# main.net
KiCad netlist of a schematic drawn in EAGLE
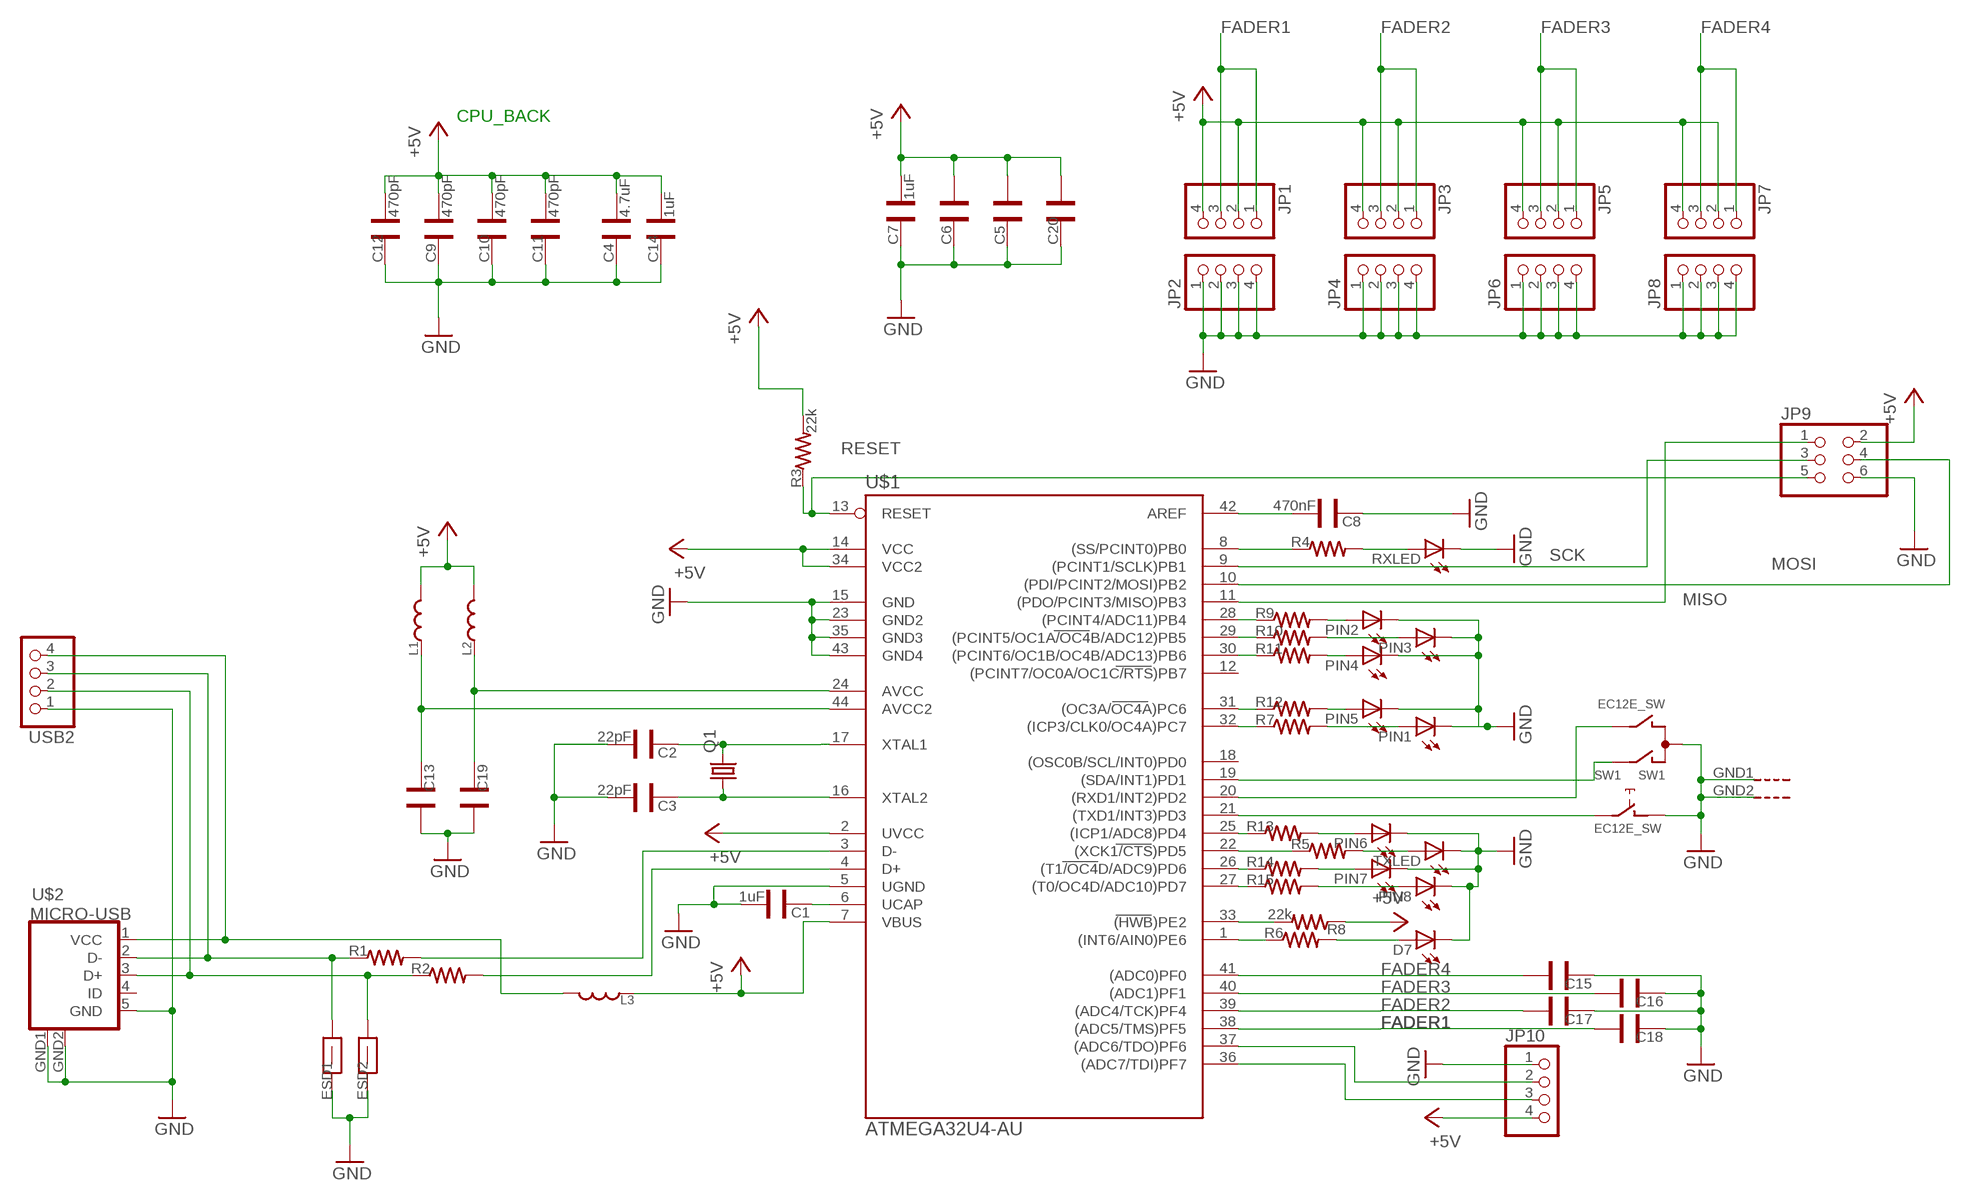
[diagram p0: schematic, sheet 1]

(export (version "E")
  (design (tool "Eeschema 10.0.6"))
  (components
    (comp (ref "C1")
      (value "1uF")
      (footprint "eagle-import:CAP-0805")
      (libsource (lib "eagle-import") (part "CAP0805"))
    )
    (comp (ref "C2")
      (value "22pF")
      (footprint "eagle-import:CAP-0603")
      (libsource (lib "eagle-import") (part "CAP0603"))
    )
    (comp (ref "C3")
      (value "22pF")
      (footprint "eagle-import:CAP-0603")
      (libsource (lib "eagle-import") (part "CAP0603"))
    )
    (comp (ref "C4")
      (value "4.7uF")
      (footprint "eagle-import:CAP-0805")
      (libsource (lib "eagle-import") (part "CAP0805"))
    )
    (comp (ref "C5")
      (value "CAP0805")
      (footprint "eagle-import:CAP-0805")
      (libsource (lib "eagle-import") (part "CAP0805"))
    )
    (comp (ref "C6")
      (value "CAP0805")
      (footprint "eagle-import:CAP-0805")
      (libsource (lib "eagle-import") (part "CAP0805"))
    )
    (comp (ref "C7")
      (value "1uF")
      (footprint "eagle-import:CAP-0805")
      (libsource (lib "eagle-import") (part "CAP0805"))
    )
    (comp (ref "C8")
      (value "470nF")
      (footprint "eagle-import:CAP-0603")
      (libsource (lib "eagle-import") (part "CAP0603"))
    )
    (comp (ref "C9")
      (value "470pF")
      (footprint "eagle-import:CAP-0603")
      (libsource (lib "eagle-import") (part "CAP0603"))
    )
    (comp (ref "C10")
      (value "470pF")
      (footprint "eagle-import:CAP-0603")
      (libsource (lib "eagle-import") (part "CAP0603"))
    )
    (comp (ref "C11")
      (value "470pF")
      (footprint "eagle-import:CAP-0603")
      (libsource (lib "eagle-import") (part "CAP0603"))
    )
    (comp (ref "C12")
      (value "470pF")
      (footprint "eagle-import:CAP-0603")
      (libsource (lib "eagle-import") (part "CAP0603"))
    )
    (comp (ref "C13")
      (value "CAP0805")
      (footprint "eagle-import:CAP-0805")
      (libsource (lib "eagle-import") (part "CAP0805"))
    )
    (comp (ref "C14")
      (value "1uF")
      (footprint "eagle-import:CAP-0805")
      (libsource (lib "eagle-import") (part "CAP0805"))
    )
    (comp (ref "C15")
      (value "CAP0603")
      (footprint "eagle-import:CAP-0603")
      (libsource (lib "eagle-import") (part "CAP0603"))
    )
    (comp (ref "C16")
      (value "CAP0603")
      (footprint "eagle-import:CAP-0603")
      (libsource (lib "eagle-import") (part "CAP0603"))
    )
    (comp (ref "C17")
      (value "CAP0603")
      (footprint "eagle-import:CAP-0603")
      (libsource (lib "eagle-import") (part "CAP0603"))
    )
    (comp (ref "C18")
      (value "CAP0603")
      (footprint "eagle-import:CAP-0603")
      (libsource (lib "eagle-import") (part "CAP0603"))
    )
    (comp (ref "C19")
      (value "CAP0805")
      (footprint "eagle-import:CAP-0805")
      (libsource (lib "eagle-import") (part "CAP0805"))
    )
    (comp (ref "C20")
      (value "CAP0805")
      (footprint "eagle-import:CAP-0805")
      (libsource (lib "eagle-import") (part "CAP0805"))
    )
    (comp (ref "D7")
      (value "LED0603")
      (footprint "eagle-import:LED-0603")
      (libsource (lib "eagle-import") (part "LED0603"))
    )
    (comp (ref "ESD1")
      (value "FB")
      (footprint "eagle-import:FB-0603")
      (libsource (lib "eagle-import") (part "FB"))
    )
    (comp (ref "ESD2")
      (value "FB")
      (footprint "eagle-import:FB-0603")
      (libsource (lib "eagle-import") (part "FB"))
    )
    (comp (ref "JP1")
      (value "PINHD-1X4")
      (footprint "eagle-import:1X04")
      (libsource (lib "eagle-import") (part "PINHD-1X4"))
    )
    (comp (ref "JP2")
      (value "PINHD-1X4")
      (footprint "eagle-import:1X04")
      (libsource (lib "eagle-import") (part "PINHD-1X4"))
    )
    (comp (ref "JP3")
      (value "PINHD-1X4")
      (footprint "eagle-import:1X04")
      (libsource (lib "eagle-import") (part "PINHD-1X4"))
    )
    (comp (ref "JP4")
      (value "PINHD-1X4")
      (footprint "eagle-import:1X04")
      (libsource (lib "eagle-import") (part "PINHD-1X4"))
    )
    (comp (ref "JP5")
      (value "PINHD-1X4")
      (footprint "eagle-import:1X04")
      (libsource (lib "eagle-import") (part "PINHD-1X4"))
    )
    (comp (ref "JP6")
      (value "PINHD-1X4")
      (footprint "eagle-import:1X04")
      (libsource (lib "eagle-import") (part "PINHD-1X4"))
    )
    (comp (ref "JP7")
      (value "PINHD-1X4")
      (footprint "eagle-import:1X04")
      (libsource (lib "eagle-import") (part "PINHD-1X4"))
    )
    (comp (ref "JP8")
      (value "PINHD-1X4")
      (footprint "eagle-import:1X04")
      (libsource (lib "eagle-import") (part "PINHD-1X4"))
    )
    (comp (ref "JP9")
      (value "PINHD-2X3")
      (footprint "eagle-import:2X03")
      (libsource (lib "eagle-import") (part "PINHD-2X3"))
    )
    (comp (ref "JP10")
      (value "PINHD-1X4")
      (footprint "eagle-import:1X04")
      (libsource (lib "eagle-import") (part "PINHD-1X4"))
    )
    (comp (ref "L1")
      (value "IND0603")
      (footprint "eagle-import:IND-0603")
      (libsource (lib "eagle-import") (part "IND0603"))
    )
    (comp (ref "L2")
      (value "IND0603")
      (footprint "eagle-import:IND-0603")
      (libsource (lib "eagle-import") (part "IND0603"))
    )
    (comp (ref "L3")
      (value "IND0603")
      (footprint "eagle-import:IND-0603")
      (libsource (lib "eagle-import") (part "IND0603"))
    )
    (comp (ref "PIN1")
      (value "LED0603")
      (footprint "eagle-import:LED-0603")
      (libsource (lib "eagle-import") (part "LED0603"))
    )
    (comp (ref "PIN2")
      (value "LED0603")
      (footprint "eagle-import:LED-0603")
      (libsource (lib "eagle-import") (part "LED0603"))
    )
    (comp (ref "PIN3")
      (value "LED0603")
      (footprint "eagle-import:LED-0603")
      (libsource (lib "eagle-import") (part "LED0603"))
    )
    (comp (ref "PIN4")
      (value "LED0603")
      (footprint "eagle-import:LED-0603")
      (libsource (lib "eagle-import") (part "LED0603"))
    )
    (comp (ref "PIN5")
      (value "LED0603")
      (footprint "eagle-import:LED-0603")
      (libsource (lib "eagle-import") (part "LED0603"))
    )
    (comp (ref "PIN6")
      (value "LED0603")
      (footprint "eagle-import:LED-0603")
      (libsource (lib "eagle-import") (part "LED0603"))
    )
    (comp (ref "PIN7")
      (value "LED0603")
      (footprint "eagle-import:LED-0603")
      (libsource (lib "eagle-import") (part "LED0603"))
    )
    (comp (ref "PIN8")
      (value "LED0603")
      (footprint "eagle-import:LED-0603")
      (libsource (lib "eagle-import") (part "LED0603"))
    )
    (comp (ref "Q1")
      (value "CRYSTALHC49S")
      (footprint "eagle-import:HC49_S")
      (libsource (lib "eagle-import") (part "CRYSTALHC49S"))
    )
    (comp (ref "R1")
      (value "RES0603")
      (footprint "eagle-import:RES-0603")
      (libsource (lib "eagle-import") (part "RES0603"))
    )
    (comp (ref "R2")
      (value "RES0603")
      (footprint "eagle-import:RES-0603")
      (libsource (lib "eagle-import") (part "RES0603"))
    )
    (comp (ref "R3")
      (value "22k")
      (footprint "eagle-import:RES-0603")
      (libsource (lib "eagle-import") (part "RES0603"))
    )
    (comp (ref "R4")
      (value "RES0603")
      (footprint "eagle-import:RES-0603")
      (libsource (lib "eagle-import") (part "RES0603"))
    )
    (comp (ref "R5")
      (value "RES0603")
      (footprint "eagle-import:RES-0603")
      (libsource (lib "eagle-import") (part "RES0603"))
    )
    (comp (ref "R6")
      (value "RES0603")
      (footprint "eagle-import:RES-0603")
      (libsource (lib "eagle-import") (part "RES0603"))
    )
    (comp (ref "R7")
      (value "RES0603")
      (footprint "eagle-import:RES-0603")
      (libsource (lib "eagle-import") (part "RES0603"))
    )
    (comp (ref "R8")
      (value "22k")
      (footprint "eagle-import:RES-0603")
      (libsource (lib "eagle-import") (part "RES0603"))
    )
    (comp (ref "R9")
      (value "RES0603")
      (footprint "eagle-import:RES-0603")
      (libsource (lib "eagle-import") (part "RES0603"))
    )
    (comp (ref "R10")
      (value "RES0603")
      (footprint "eagle-import:RES-0603")
      (libsource (lib "eagle-import") (part "RES0603"))
    )
    (comp (ref "R11")
      (value "RES0603")
      (footprint "eagle-import:RES-0603")
      (libsource (lib "eagle-import") (part "RES0603"))
    )
    (comp (ref "R12")
      (value "RES0603")
      (footprint "eagle-import:RES-0603")
      (libsource (lib "eagle-import") (part "RES0603"))
    )
    (comp (ref "R13")
      (value "RES0603")
      (footprint "eagle-import:RES-0603")
      (libsource (lib "eagle-import") (part "RES0603"))
    )
    (comp (ref "R14")
      (value "RES0603")
      (footprint "eagle-import:RES-0603")
      (libsource (lib "eagle-import") (part "RES0603"))
    )
    (comp (ref "R15")
      (value "RES0603")
      (footprint "eagle-import:RES-0603")
      (libsource (lib "eagle-import") (part "RES0603"))
    )
    (comp (ref "RXLED")
      (value "LED0603")
      (footprint "eagle-import:LED-0603")
      (libsource (lib "eagle-import") (part "LED0603"))
    )
    (comp (ref "SW1")
      (value "EC12E_SW")
      (footprint "eagle-import:ALPS_EC12E_SW")
      (fields (field (name "MPN") "EC12E2424407"))
      (libsource (lib "eagle-import") (part "EC12E_SW"))
    )
    (comp (ref "TXLED")
      (value "LED0603")
      (footprint "eagle-import:LED-0603")
      (libsource (lib "eagle-import") (part "LED0603"))
    )
    (comp (ref "U$1")
      (value "ATMEGA32U4-AU")
      (footprint "eagle-import:TQFP44")
      (libsource (lib "eagle-import") (part "ATMEGA32U4-AU"))
    )
    (comp (ref "U$2")
      (value "MICRO-USB")
      (footprint "eagle-import:MICRO-USB")
      (libsource (lib "eagle-import") (part "MICRO-USB"))
    )
    (comp (ref "USB2")
      (value "PINHD-1X4")
      (footprint "eagle-import:1X04")
      (libsource (lib "eagle-import") (part "PINHD-1X4"))
    )
  )
  (nets
    (net (code "1") (name "+5V") (class "Default")
      (node (ref "C10") (pin "1") (pinfunction "1_1") (pintype "passive"))
      (node (ref "C11") (pin "1") (pinfunction "1_1") (pintype "passive"))
      (node (ref "C12") (pin "1") (pinfunction "1_1") (pintype "passive"))
      (node (ref "C14") (pin "1") (pinfunction "1_1") (pintype "passive"))
      (node (ref "C20") (pin "1") (pinfunction "1_1") (pintype "passive"))
      (node (ref "C4") (pin "1") (pinfunction "1_1") (pintype "passive"))
      (node (ref "C5") (pin "1") (pinfunction "1_1") (pintype "passive"))
      (node (ref "C6") (pin "1") (pinfunction "1_1") (pintype "passive"))
      (node (ref "C7") (pin "1") (pinfunction "1_1") (pintype "passive"))
      (node (ref "C9") (pin "1") (pinfunction "1_1") (pintype "passive"))
      (node (ref "JP1") (pin "2") (pinfunction "2_2") (pintype "passive"))
      (node (ref "JP1") (pin "4") (pinfunction "4_4") (pintype "passive"))
      (node (ref "JP10") (pin "4") (pinfunction "4_4") (pintype "passive"))
      (node (ref "JP3") (pin "2") (pinfunction "2_2") (pintype "passive"))
      (node (ref "JP3") (pin "4") (pinfunction "4_4") (pintype "passive"))
      (node (ref "JP5") (pin "2") (pinfunction "2_2") (pintype "passive"))
      (node (ref "JP5") (pin "4") (pinfunction "4_4") (pintype "passive"))
      (node (ref "JP7") (pin "2") (pinfunction "2_2") (pintype "passive"))
      (node (ref "JP7") (pin "4") (pinfunction "4_4") (pintype "passive"))
      (node (ref "JP9") (pin "2") (pinfunction "2_2") (pintype "passive"))
      (node (ref "L1") (pin "1") (pinfunction "1_1") (pintype "passive"))
      (node (ref "L2") (pin "1") (pinfunction "1_1") (pintype "passive"))
      (node (ref "L3") (pin "2") (pinfunction "2_2") (pintype "passive"))
      (node (ref "R3") (pin "2") (pinfunction "2_2") (pintype "passive"))
      (node (ref "R8") (pin "1") (pinfunction "1_1") (pintype "passive"))
      (node (ref "U$1") (pin "14") (pinfunction "VCC_14") (pintype "bidirectional"))
      (node (ref "U$1") (pin "2") (pinfunction "UVCC_2") (pintype "bidirectional"))
      (node (ref "U$1") (pin "34") (pinfunction "VCC2_34") (pintype "bidirectional"))
      (node (ref "U$1") (pin "7") (pinfunction "VBUS_7") (pintype "bidirectional"))
    )
    (net (code "2") (name "/FADER1") (class "Default")
      (node (ref "C18") (pin "1") (pinfunction "1_1") (pintype "passive"))
      (node (ref "JP1") (pin "1") (pinfunction "1_1") (pintype "passive"))
      (node (ref "JP1") (pin "3") (pinfunction "3_3") (pintype "passive"))
      (node (ref "U$1") (pin "38") (pinfunction "(ADC5/TMS)PF5_38") (pintype "bidirectional"))
    )
    (net (code "3") (name "/FADER2") (class "Default")
      (node (ref "C17") (pin "1") (pinfunction "1_1") (pintype "passive"))
      (node (ref "JP3") (pin "1") (pinfunction "1_1") (pintype "passive"))
      (node (ref "JP3") (pin "3") (pinfunction "3_3") (pintype "passive"))
      (node (ref "U$1") (pin "39") (pinfunction "(ADC4/TCK)PF4_39") (pintype "bidirectional"))
    )
    (net (code "4") (name "/FADER3") (class "Default")
      (node (ref "C16") (pin "1") (pinfunction "1_1") (pintype "passive"))
      (node (ref "JP5") (pin "1") (pinfunction "1_1") (pintype "passive"))
      (node (ref "JP5") (pin "3") (pinfunction "3_3") (pintype "passive"))
      (node (ref "U$1") (pin "40") (pinfunction "(ADC1)PF1_40") (pintype "bidirectional"))
    )
    (net (code "5") (name "/FADER4") (class "Default")
      (node (ref "C15") (pin "1") (pinfunction "1_1") (pintype "passive"))
      (node (ref "JP7") (pin "1") (pinfunction "1_1") (pintype "passive"))
      (node (ref "JP7") (pin "3") (pinfunction "3_3") (pintype "passive"))
      (node (ref "U$1") (pin "41") (pinfunction "(ADC0)PF0_41") (pintype "bidirectional"))
    )
    (net (code "6") (name "/MISO") (class "Default")
      (node (ref "JP9") (pin "1") (pinfunction "1_1") (pintype "passive"))
      (node (ref "U$1") (pin "11") (pinfunction "(PDO/PCINT3/MISO)PB3_11") (pintype "bidirectional"))
    )
    (net (code "7") (name "/MOSI") (class "Default")
      (node (ref "JP9") (pin "4") (pinfunction "4_4") (pintype "passive"))
      (node (ref "U$1") (pin "10") (pinfunction "(PDI/PCINT2/MOSI)PB2_10") (pintype "bidirectional"))
    )
    (net (code "8") (name "/RESET") (class "Default")
      (node (ref "JP9") (pin "5") (pinfunction "5_5") (pintype "passive"))
      (node (ref "R3") (pin "1") (pinfunction "1_1") (pintype "passive"))
      (node (ref "U$1") (pin "13") (pinfunction "RESET_13") (pintype "bidirectional"))
    )
    (net (code "9") (name "/SCK") (class "Default")
      (node (ref "JP9") (pin "3") (pinfunction "3_3") (pintype "passive"))
      (node (ref "U$1") (pin "9") (pinfunction "(PCINT1/SCLK)PB1_9") (pintype "bidirectional"))
    )
    (net (code "10") (name "GND") (class "Default")
      (node (ref "C1") (pin "1") (pinfunction "1_1") (pintype "passive"))
      (node (ref "C10") (pin "2") (pinfunction "2_2") (pintype "passive"))
      (node (ref "C11") (pin "2") (pinfunction "2_2") (pintype "passive"))
      (node (ref "C12") (pin "2") (pinfunction "2_2") (pintype "passive"))
      (node (ref "C13") (pin "1") (pinfunction "1_1") (pintype "passive"))
      (node (ref "C14") (pin "2") (pinfunction "2_2") (pintype "passive"))
      (node (ref "C15") (pin "2") (pinfunction "2_2") (pintype "passive"))
      (node (ref "C16") (pin "2") (pinfunction "2_2") (pintype "passive"))
      (node (ref "C17") (pin "2") (pinfunction "2_2") (pintype "passive"))
      (node (ref "C18") (pin "2") (pinfunction "2_2") (pintype "passive"))
      (node (ref "C19") (pin "1") (pinfunction "1_1") (pintype "passive"))
      (node (ref "C2") (pin "1") (pinfunction "1_1") (pintype "passive"))
      (node (ref "C20") (pin "2") (pinfunction "2_2") (pintype "passive"))
      (node (ref "C3") (pin "1") (pinfunction "1_1") (pintype "passive"))
      (node (ref "C4") (pin "2") (pinfunction "2_2") (pintype "passive"))
      (node (ref "C5") (pin "2") (pinfunction "2_2") (pintype "passive"))
      (node (ref "C6") (pin "2") (pinfunction "2_2") (pintype "passive"))
      (node (ref "C7") (pin "2") (pinfunction "2_2") (pintype "passive"))
      (node (ref "C8") (pin "2") (pinfunction "2_2") (pintype "passive"))
      (node (ref "C9") (pin "2") (pinfunction "2_2") (pintype "passive"))
      (node (ref "D7") (pin "C") (pinfunction "C_C") (pintype "passive"))
      (node (ref "ESD1") (pin "1") (pinfunction "P$1_1") (pintype "passive"))
      (node (ref "ESD2") (pin "1") (pinfunction "P$1_1") (pintype "passive"))
      (node (ref "JP10") (pin "1") (pinfunction "1_1") (pintype "passive"))
      (node (ref "JP2") (pin "1") (pinfunction "1_1") (pintype "passive"))
      (node (ref "JP2") (pin "2") (pinfunction "2_2") (pintype "passive"))
      (node (ref "JP2") (pin "3") (pinfunction "3_3") (pintype "passive"))
      (node (ref "JP2") (pin "4") (pinfunction "4_4") (pintype "passive"))
      (node (ref "JP4") (pin "1") (pinfunction "1_1") (pintype "passive"))
      (node (ref "JP4") (pin "2") (pinfunction "2_2") (pintype "passive"))
      (node (ref "JP4") (pin "3") (pinfunction "3_3") (pintype "passive"))
      (node (ref "JP4") (pin "4") (pinfunction "4_4") (pintype "passive"))
      (node (ref "JP6") (pin "1") (pinfunction "1_1") (pintype "passive"))
      (node (ref "JP6") (pin "2") (pinfunction "2_2") (pintype "passive"))
      (node (ref "JP6") (pin "3") (pinfunction "3_3") (pintype "passive"))
      (node (ref "JP6") (pin "4") (pinfunction "4_4") (pintype "passive"))
      (node (ref "JP8") (pin "1") (pinfunction "1_1") (pintype "passive"))
      (node (ref "JP8") (pin "2") (pinfunction "2_2") (pintype "passive"))
      (node (ref "JP8") (pin "3") (pinfunction "3_3") (pintype "passive"))
      (node (ref "JP8") (pin "4") (pinfunction "4_4") (pintype "passive"))
      (node (ref "JP9") (pin "6") (pinfunction "6_6") (pintype "passive"))
      (node (ref "PIN1") (pin "C") (pinfunction "C_C") (pintype "passive"))
      (node (ref "PIN2") (pin "C") (pinfunction "C_C") (pintype "passive"))
      (node (ref "PIN3") (pin "C") (pinfunction "C_C") (pintype "passive"))
      (node (ref "PIN4") (pin "C") (pinfunction "C_C") (pintype "passive"))
      (node (ref "PIN5") (pin "C") (pinfunction "C_C") (pintype "passive"))
      (node (ref "PIN6") (pin "C") (pinfunction "C_C") (pintype "passive"))
      (node (ref "PIN7") (pin "C") (pinfunction "C_C") (pintype "passive"))
      (node (ref "PIN8") (pin "C") (pinfunction "C_C") (pintype "passive"))
      (node (ref "RXLED") (pin "C") (pinfunction "C_C") (pintype "passive"))
      (node (ref "SW1") (pin "C") (pinfunction "C_C") (pintype "passive"))
      (node (ref "SW1") (pin "D") (pinfunction "1_D") (pintype "passive"))
      (node (ref "SW1") (pin "GND1") (pinfunction "G_GND1") (pintype "passive"))
      (node (ref "SW1") (pin "GND2") (pinfunction "G_GND2") (pintype "passive"))
      (node (ref "TXLED") (pin "C") (pinfunction "C_C") (pintype "passive"))
      (node (ref "U$1") (pin "15") (pinfunction "GND_15") (pintype "bidirectional"))
      (node (ref "U$1") (pin "23") (pinfunction "GND2_23") (pintype "bidirectional"))
      (node (ref "U$1") (pin "35") (pinfunction "GND3_35") (pintype "bidirectional"))
      (node (ref "U$1") (pin "43") (pinfunction "GND4_43") (pintype "bidirectional"))
      (node (ref "U$1") (pin "5") (pinfunction "UGND_5") (pintype "bidirectional"))
      (node (ref "U$2") (pin "5") (pinfunction "GND_5") (pintype "power_in"))
      (node (ref "U$2") (pin "GND1") (pinfunction "GND_GND1") (pintype "power_in"))
      (node (ref "U$2") (pin "GND2") (pinfunction "GND_GND2") (pintype "power_in"))
      (node (ref "USB2") (pin "1") (pinfunction "1_1") (pintype "passive"))
    )
    (net (code "11") (name "Net-(D7-PadA)") (class "Default")
      (node (ref "D7") (pin "A") (pinfunction "A_A") (pintype "passive"))
      (node (ref "R6") (pin "2") (pinfunction "2_2") (pintype "passive"))
    )
    (net (code "12") (name "Net-(ESD1-P$2)") (class "Default")
      (node (ref "ESD1") (pin "2") (pinfunction "P$2_2") (pintype "bidirectional"))
      (node (ref "R1") (pin "1") (pinfunction "1_1") (pintype "passive"))
      (node (ref "U$2") (pin "2") (pinfunction "D-_2") (pintype "bidirectional"))
      (node (ref "USB2") (pin "3") (pinfunction "3_3") (pintype "passive"))
    )
    (net (code "13") (name "Net-(ESD2-P$2)") (class "Default")
      (node (ref "ESD2") (pin "2") (pinfunction "P$2_2") (pintype "bidirectional"))
      (node (ref "R2") (pin "1") (pinfunction "1_1") (pintype "passive"))
      (node (ref "U$2") (pin "3") (pinfunction "D+_3") (pintype "bidirectional"))
      (node (ref "USB2") (pin "2") (pinfunction "2_2") (pintype "passive"))
    )
    (net (code "14") (name "Net-(PIN1-PadA)") (class "Default")
      (node (ref "PIN1") (pin "A") (pinfunction "A_A") (pintype "passive"))
      (node (ref "R7") (pin "2") (pinfunction "2_2") (pintype "passive"))
    )
    (net (code "15") (name "Net-(PIN2-PadA)") (class "Default")
      (node (ref "PIN2") (pin "A") (pinfunction "A_A") (pintype "passive"))
      (node (ref "R9") (pin "2") (pinfunction "2_2") (pintype "passive"))
    )
    (net (code "16") (name "Net-(PIN3-PadA)") (class "Default")
      (node (ref "PIN3") (pin "A") (pinfunction "A_A") (pintype "passive"))
      (node (ref "R10") (pin "2") (pinfunction "2_2") (pintype "passive"))
    )
    (net (code "17") (name "Net-(PIN4-PadA)") (class "Default")
      (node (ref "PIN4") (pin "A") (pinfunction "A_A") (pintype "passive"))
      (node (ref "R11") (pin "2") (pinfunction "2_2") (pintype "passive"))
    )
    (net (code "18") (name "Net-(PIN5-PadA)") (class "Default")
      (node (ref "PIN5") (pin "A") (pinfunction "A_A") (pintype "passive"))
      (node (ref "R12") (pin "2") (pinfunction "2_2") (pintype "passive"))
    )
    (net (code "19") (name "Net-(PIN6-PadA)") (class "Default")
      (node (ref "PIN6") (pin "A") (pinfunction "A_A") (pintype "passive"))
      (node (ref "R13") (pin "2") (pinfunction "2_2") (pintype "passive"))
    )
    (net (code "20") (name "Net-(PIN7-PadA)") (class "Default")
      (node (ref "PIN7") (pin "A") (pinfunction "A_A") (pintype "passive"))
      (node (ref "R14") (pin "2") (pinfunction "2_2") (pintype "passive"))
    )
    (net (code "21") (name "Net-(PIN8-PadA)") (class "Default")
      (node (ref "PIN8") (pin "A") (pinfunction "A_A") (pintype "passive"))
      (node (ref "R15") (pin "2") (pinfunction "2_2") (pintype "passive"))
    )
    (net (code "22") (name "Net-(R4-Pad2)") (class "Default")
      (node (ref "R4") (pin "2") (pinfunction "2_2") (pintype "passive"))
      (node (ref "RXLED") (pin "A") (pinfunction "A_A") (pintype "passive"))
    )
    (net (code "23") (name "Net-(R5-Pad2)") (class "Default")
      (node (ref "R5") (pin "2") (pinfunction "2_2") (pintype "passive"))
      (node (ref "TXLED") (pin "A") (pinfunction "A_A") (pintype "passive"))
    )
    (net (code "24") (name "Net-(SW1B-2)") (class "Default")
      (node (ref "SW1") (pin "E") (pinfunction "2_E") (pintype "passive"))
      (node (ref "U$1") (pin "21") (pinfunction "(TXD1/INT3)PD3_21") (pintype "bidirectional"))
    )
    (net (code "25") (name "Net-(U$1-(ADC6{slash}TDO)PF6)") (class "Default")
      (node (ref "JP10") (pin "2") (pinfunction "2_2") (pintype "passive"))
      (node (ref "U$1") (pin "37") (pinfunction "(ADC6/TDO)PF6_37") (pintype "bidirectional"))
    )
    (net (code "26") (name "Net-(U$1-(ADC7{slash}TDI)PF7)") (class "Default")
      (node (ref "JP10") (pin "3") (pinfunction "3_3") (pintype "passive"))
      (node (ref "U$1") (pin "36") (pinfunction "(ADC7/TDI)PF7_36") (pintype "bidirectional"))
    )
    (net (code "27") (name "Net-(U$1-(HWB)PE2)") (class "Default")
      (node (ref "R8") (pin "2") (pinfunction "2_2") (pintype "passive"))
      (node (ref "U$1") (pin "33") (pinfunction "(HWB)PE2_33") (pintype "bidirectional"))
    )
    (net (code "28") (name "Net-(U$1-(ICP1{slash}ADC8)PD4)") (class "Default")
      (node (ref "R13") (pin "1") (pinfunction "1_1") (pintype "passive"))
      (node (ref "U$1") (pin "25") (pinfunction "(ICP1/ADC8)PD4_25") (pintype "bidirectional"))
    )
    (net (code "29") (name "Net-(U$1-(ICP3{slash}CLK0{slash}OC4A)PC7)") (class "Default")
      (node (ref "R7") (pin "1") (pinfunction "1_1") (pintype "passive"))
      (node (ref "U$1") (pin "32") (pinfunction "(ICP3/CLK0/OC4A)PC7_32") (pintype "bidirectional"))
    )
    (net (code "30") (name "Net-(U$1-(INT6{slash}AIN0)PE6)") (class "Default")
      (node (ref "R6") (pin "1") (pinfunction "1_1") (pintype "passive"))
      (node (ref "U$1") (pin "1") (pinfunction "(INT6/AIN0)PE6_1") (pintype "bidirectional"))
    )
    (net (code "31") (name "Net-(U$1-(OC3A{slash}OC4A)PC6)") (class "Default")
      (node (ref "R12") (pin "1") (pinfunction "1_1") (pintype "passive"))
      (node (ref "U$1") (pin "31") (pinfunction "(OC3A/OC4A)PC6_31") (pintype "bidirectional"))
    )
    (net (code "32") (name "Net-(U$1-(PCINT4{slash}ADC11)PB4)") (class "Default")
      (node (ref "R9") (pin "1") (pinfunction "1_1") (pintype "passive"))
      (node (ref "U$1") (pin "28") (pinfunction "(PCINT4/ADC11)PB4_28") (pintype "bidirectional"))
    )
    (net (code "33") (name "Net-(U$1-(PCINT5{slash}OC1A{slash}OC4B{slash}ADC12)PB5)") (class "Default")
      (node (ref "R10") (pin "1") (pinfunction "1_1") (pintype "passive"))
      (node (ref "U$1") (pin "29") (pinfunction "(PCINT5/OC1A/OC4B/ADC12)PB5_29") (pintype "bidirectional"))
    )
    (net (code "34") (name "Net-(U$1-(PCINT6{slash}OC1B{slash}OC4B{slash}ADC13)PB6)") (class "Default")
      (node (ref "R11") (pin "1") (pinfunction "1_1") (pintype "passive"))
      (node (ref "U$1") (pin "30") (pinfunction "(PCINT6/OC1B/OC4B/ADC13)PB6_30") (pintype "bidirectional"))
    )
    (net (code "35") (name "Net-(U$1-(RXD1{slash}INT2)PD2)") (class "Default")
      (node (ref "SW1") (pin "B") (pinfunction "B_B") (pintype "passive"))
      (node (ref "U$1") (pin "20") (pinfunction "(RXD1/INT2)PD2_20") (pintype "bidirectional"))
    )
    (net (code "36") (name "Net-(U$1-(SDA{slash}INT1)PD1)") (class "Default")
      (node (ref "SW1") (pin "A") (pinfunction "A_A") (pintype "passive"))
      (node (ref "U$1") (pin "19") (pinfunction "(SDA/INT1)PD1_19") (pintype "bidirectional"))
    )
    (net (code "37") (name "Net-(U$1-(SS{slash}PCINT0)PB0)") (class "Default")
      (node (ref "R4") (pin "1") (pinfunction "1_1") (pintype "passive"))
      (node (ref "U$1") (pin "8") (pinfunction "(SS/PCINT0)PB0_8") (pintype "bidirectional"))
    )
    (net (code "38") (name "Net-(U$1-(T0{slash}OC4D{slash}ADC10)PD7)") (class "Default")
      (node (ref "R15") (pin "1") (pinfunction "1_1") (pintype "passive"))
      (node (ref "U$1") (pin "27") (pinfunction "(T0/OC4D/ADC10)PD7_27") (pintype "bidirectional"))
    )
    (net (code "39") (name "Net-(U$1-(T1{slash}OC4D{slash}ADC9)PD6)") (class "Default")
      (node (ref "R14") (pin "1") (pinfunction "1_1") (pintype "passive"))
      (node (ref "U$1") (pin "26") (pinfunction "(T1/OC4D/ADC9)PD6_26") (pintype "bidirectional"))
    )
    (net (code "40") (name "Net-(U$1-(XCK1{slash}CTS)PD5)") (class "Default")
      (node (ref "R5") (pin "1") (pinfunction "1_1") (pintype "passive"))
      (node (ref "U$1") (pin "22") (pinfunction "(XCK1/CTS)PD5_22") (pintype "bidirectional"))
    )
    (net (code "41") (name "Net-(U$1-AREF)") (class "Default")
      (node (ref "C8") (pin "1") (pinfunction "1_1") (pintype "passive"))
      (node (ref "U$1") (pin "42") (pinfunction "AREF_42") (pintype "bidirectional"))
    )
    (net (code "42") (name "Net-(U$1-AVCC)") (class "Default")
      (node (ref "C19") (pin "2") (pinfunction "2_2") (pintype "passive"))
      (node (ref "L2") (pin "2") (pinfunction "2_2") (pintype "passive"))
      (node (ref "U$1") (pin "24") (pinfunction "AVCC_24") (pintype "bidirectional"))
    )
    (net (code "43") (name "Net-(U$1-AVCC2)") (class "Default")
      (node (ref "C13") (pin "2") (pinfunction "2_2") (pintype "passive"))
      (node (ref "L1") (pin "2") (pinfunction "2_2") (pintype "passive"))
      (node (ref "U$1") (pin "44") (pinfunction "AVCC2_44") (pintype "bidirectional"))
    )
    (net (code "44") (name "Net-(U$1-D+)") (class "Default")
      (node (ref "R2") (pin "2") (pinfunction "2_2") (pintype "passive"))
      (node (ref "U$1") (pin "4") (pinfunction "D+_4") (pintype "bidirectional"))
    )
    (net (code "45") (name "Net-(U$1-D-)") (class "Default")
      (node (ref "R1") (pin "2") (pinfunction "2_2") (pintype "passive"))
      (node (ref "U$1") (pin "3") (pinfunction "D-_3") (pintype "bidirectional"))
    )
    (net (code "46") (name "Net-(U$1-UCAP)") (class "Default")
      (node (ref "C1") (pin "2") (pinfunction "2_2") (pintype "passive"))
      (node (ref "U$1") (pin "6") (pinfunction "UCAP_6") (pintype "bidirectional"))
    )
    (net (code "47") (name "Net-(U$1-XTAL1)") (class "Default")
      (node (ref "C2") (pin "2") (pinfunction "2_2") (pintype "passive"))
      (node (ref "Q1") (pin "2") (pinfunction "2_2") (pintype "passive"))
      (node (ref "U$1") (pin "17") (pinfunction "XTAL1_17") (pintype "bidirectional"))
    )
    (net (code "48") (name "Net-(U$1-XTAL2)") (class "Default")
      (node (ref "C3") (pin "2") (pinfunction "2_2") (pintype "passive"))
      (node (ref "Q1") (pin "1") (pinfunction "1_1") (pintype "passive"))
      (node (ref "U$1") (pin "16") (pinfunction "XTAL2_16") (pintype "bidirectional"))
    )
    (net (code "49") (name "Net-(U$2-VCC)") (class "Default")
      (node (ref "L3") (pin "1") (pinfunction "1_1") (pintype "passive"))
      (node (ref "U$2") (pin "1") (pinfunction "VCC_1") (pintype "power_in"))
      (node (ref "USB2") (pin "4") (pinfunction "4_4") (pintype "passive"))
    )
    (net (code "50") (name "unconnected-(U$1-(OSC0B{slash}SCL{slash}INT0)PD0-Pad18)") (class "Default")
      (node (ref "U$1") (pin "18") (pinfunction "(OSC0B/SCL/INT0)PD0_18") (pintype "bidirectional"))
    )
    (net (code "51") (name "unconnected-(U$1-(PCINT7{slash}OC0A{slash}OC1C{slash}RTS)PB7-Pad12)") (class "Default")
      (node (ref "U$1") (pin "12") (pinfunction "(PCINT7/OC0A/OC1C/RTS)PB7_12") (pintype "bidirectional"))
    )
    (net (code "52") (name "unconnected-(U$2-ID-Pad4)") (class "Default")
      (node (ref "U$2") (pin "4") (pinfunction "ID_4") (pintype "bidirectional"))
    )
  )
)
